# Sheet2.net
KiCad netlist of a schematic drawn in Altium Designer
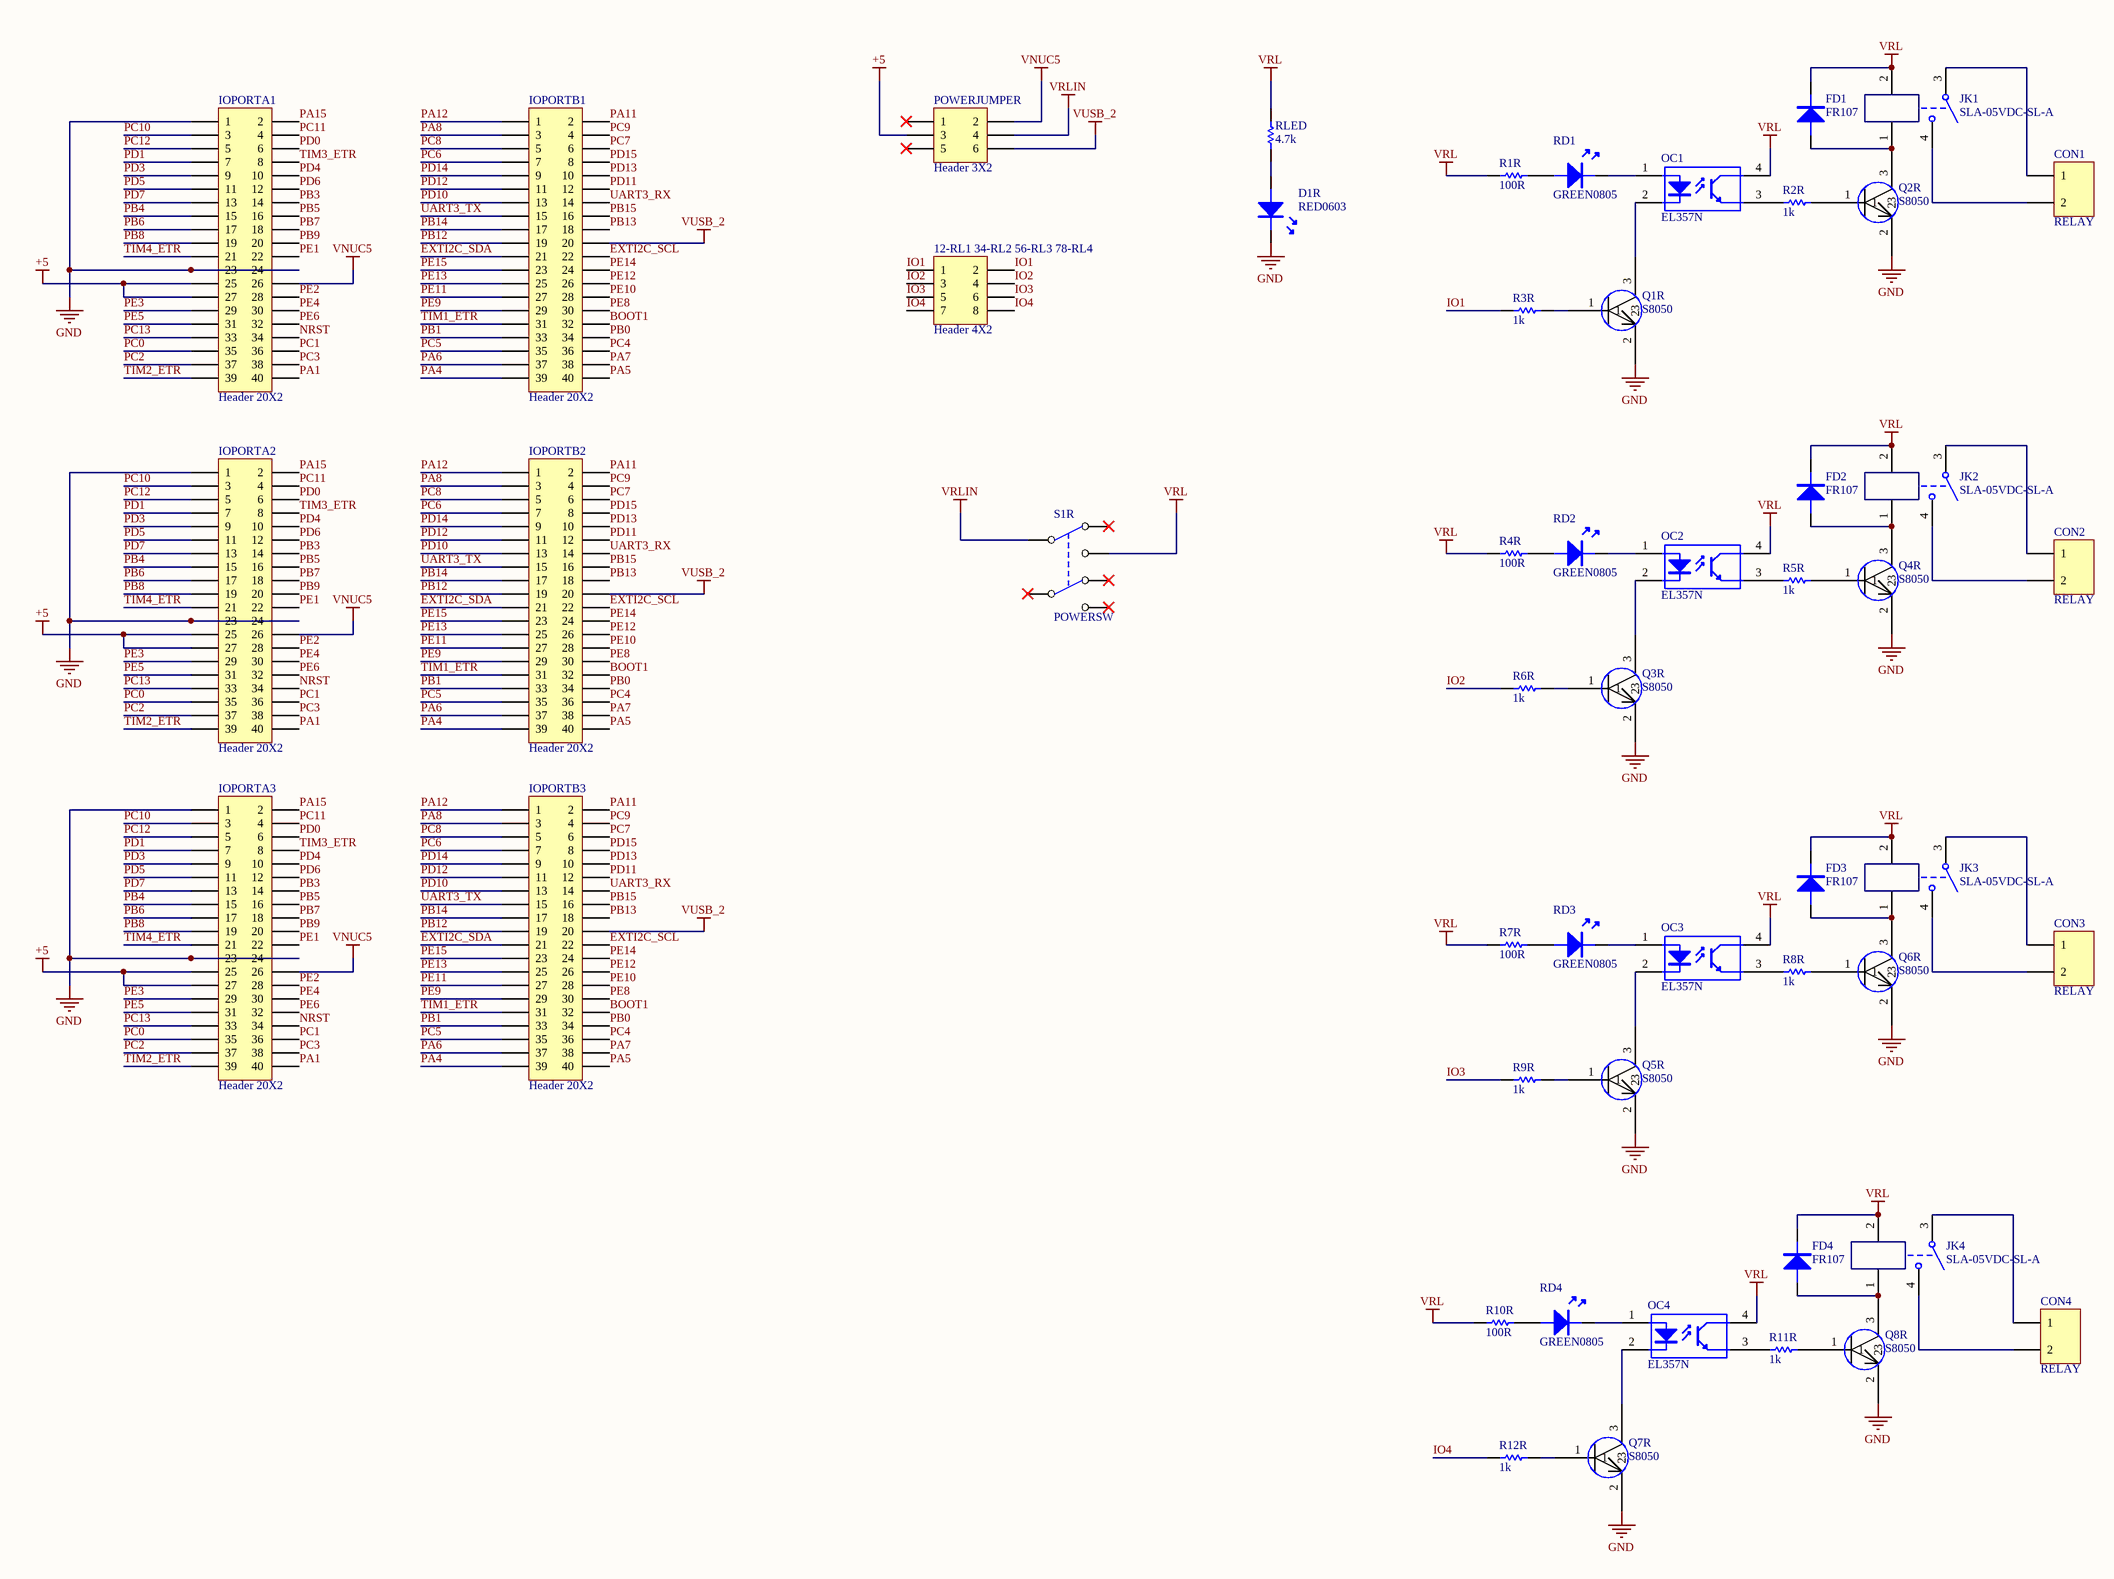
[diagram p0: Sheet2.SchDoc]

(export (version "E")
  (design (tool "Eeschema 10.0.6"))
  (components
    (comp (ref "12-RL1 34-RL2 56-RL3 78-RL4")
      (value "Header 4X2")
      (footprint "HDR2X4")
      (description "Header, 4-Pin, Dual row")
      (fields (field (name "PUBLISHER") "Altium Limited"))
      (libsource (lib "Miscellaneous Connectors") (part "Header 4X2"))
    )
    (comp (ref "CON1") (value "RELAY") (footprint "KF301-2P") (libsource (lib "接线端子") (part "Connector-2P")))
    (comp (ref "CON2") (value "RELAY") (footprint "KF301-2P") (libsource (lib "接线端子") (part "Connector-2P")))
    (comp (ref "CON3") (value "RELAY") (footprint "KF301-2P") (libsource (lib "接线端子") (part "Connector-2P")))
    (comp (ref "CON4") (value "RELAY") (footprint "KF301-2P") (libsource (lib "接线端子") (part "Connector-2P")))
    (comp (ref "D1R") (value "RED0603") (footprint "LED-0603W") (libsource (lib "LED") (part "LED")))
    (comp (ref "FD1")
      (value "FR107")
      (footprint "SOD-123")
      (description "普通二极管")
      (libsource (lib "DIODE") (part "DIODE"))
    )
    (comp (ref "FD2")
      (value "FR107")
      (footprint "SOD-123")
      (description "普通二极管")
      (libsource (lib "DIODE") (part "DIODE"))
    )
    (comp (ref "FD3")
      (value "FR107")
      (footprint "SOD-123")
      (description "普通二极管")
      (libsource (lib "DIODE") (part "DIODE"))
    )
    (comp (ref "FD4")
      (value "FR107")
      (footprint "SOD-123")
      (description "普通二极管")
      (libsource (lib "DIODE") (part "DIODE"))
    )
    (comp (ref "IOPORTA1")
      (value "Header 20X2")
      (footprint "HDR2X20")
      (description "Header, 20-Pin, Dual row")
      (fields (field (name "PUBLISHER") "Altium Limited"))
      (libsource (lib "Miscellaneous Connectors") (part "Header 20X2"))
    )
    (comp (ref "IOPORTA2")
      (value "Header 20X2")
      (footprint "HDR2X20")
      (description "Header, 20-Pin, Dual row")
      (fields (field (name "PUBLISHER") "Altium Limited"))
      (libsource (lib "Miscellaneous Connectors") (part "Header 20X2"))
    )
    (comp (ref "IOPORTA3")
      (value "Header 20X2")
      (footprint "HDR2X20")
      (description "Header, 20-Pin, Dual row")
      (fields (field (name "PUBLISHER") "Altium Limited"))
      (libsource (lib "Miscellaneous Connectors") (part "Header 20X2"))
    )
    (comp (ref "IOPORTB1")
      (value "Header 20X2")
      (footprint "HDR2X20")
      (description "Header, 20-Pin, Dual row")
      (fields (field (name "PUBLISHER") "Altium Limited"))
      (libsource (lib "Miscellaneous Connectors") (part "Header 20X2"))
    )
    (comp (ref "IOPORTB2")
      (value "Header 20X2")
      (footprint "HDR2X20")
      (description "Header, 20-Pin, Dual row")
      (fields (field (name "PUBLISHER") "Altium Limited"))
      (libsource (lib "Miscellaneous Connectors") (part "Header 20X2"))
    )
    (comp (ref "IOPORTB3")
      (value "Header 20X2")
      (footprint "HDR2X20")
      (description "Header, 20-Pin, Dual row")
      (fields (field (name "PUBLISHER") "Altium Limited"))
      (libsource (lib "Miscellaneous Connectors") (part "Header 20X2"))
    )
    (comp (ref "JK1")
      (value "SLA-05VDC-SL-A")
      (footprint "SLA-xxVDC-SL-A")
      (description "5V常开")
      (libsource (lib "REALY") (part "SLA-05VDC-SL-A"))
    )
    (comp (ref "JK2")
      (value "SLA-05VDC-SL-A")
      (footprint "SLA-xxVDC-SL-A")
      (description "5V常开")
      (libsource (lib "REALY") (part "SLA-05VDC-SL-A"))
    )
    (comp (ref "JK3")
      (value "SLA-05VDC-SL-A")
      (footprint "SLA-xxVDC-SL-A")
      (description "5V常开")
      (libsource (lib "REALY") (part "SLA-05VDC-SL-A"))
    )
    (comp (ref "JK4")
      (value "SLA-05VDC-SL-A")
      (footprint "SLA-xxVDC-SL-A")
      (description "5V常开")
      (libsource (lib "REALY") (part "SLA-05VDC-SL-A"))
    )
    (comp (ref "OC1")
      (value "EL357N")
      (footprint "SMD_EL357N")
      (description "线性光耦")
      (libsource (lib "光电隔离器") (part "EL357N"))
    )
    (comp (ref "OC2")
      (value "EL357N")
      (footprint "SMD_EL357N")
      (description "线性光耦")
      (libsource (lib "光电隔离器") (part "EL357N"))
    )
    (comp (ref "OC3")
      (value "EL357N")
      (footprint "SMD_EL357N")
      (description "线性光耦")
      (libsource (lib "光电隔离器") (part "EL357N"))
    )
    (comp (ref "OC4")
      (value "EL357N")
      (footprint "SMD_EL357N")
      (description "线性光耦")
      (libsource (lib "光电隔离器") (part "EL357N"))
    )
    (comp (ref "POWERJUMPER")
      (value "Header 3X2")
      (footprint "HDR2X3")
      (description "Header, 3-Pin, Dual row")
      (fields (field (name "PUBLISHER") "Altium Limited"))
      (libsource (lib "Miscellaneous Connectors") (part "Header 3X2"))
    )
    (comp (ref "Q1R") (value "S8050") (footprint "ics:SOT23") (libsource (lib "ics") (part "S9014")))
    (comp (ref "Q2R") (value "S8050") (footprint "ics:SOT23") (libsource (lib "ics") (part "S9014")))
    (comp (ref "Q3R") (value "S8050") (footprint "ics:SOT23") (libsource (lib "ics") (part "S9014")))
    (comp (ref "Q4R") (value "S8050") (footprint "ics:SOT23") (libsource (lib "ics") (part "S9014")))
    (comp (ref "Q5R") (value "S8050") (footprint "ics:SOT23") (libsource (lib "ics") (part "S9014")))
    (comp (ref "Q6R") (value "S8050") (footprint "ics:SOT23") (libsource (lib "ics") (part "S9014")))
    (comp (ref "Q7R") (value "S8050") (footprint "ics:SOT23") (libsource (lib "ics") (part "S9014")))
    (comp (ref "Q8R") (value "S8050") (footprint "ics:SOT23") (libsource (lib "ics") (part "S9014")))
    (comp (ref "R1R") (value "100R") (footprint "0603R") (libsource (lib "Resistance") (part "RES")))
    (comp (ref "R2R") (value "1k") (footprint "0603R") (libsource (lib "Resistance") (part "RES")))
    (comp (ref "R3R") (value "1k") (footprint "0603R") (libsource (lib "Resistance") (part "RES")))
    (comp (ref "R4R") (value "100R") (footprint "0603R") (libsource (lib "Resistance") (part "RES")))
    (comp (ref "R5R") (value "1k") (footprint "0603R") (libsource (lib "Resistance") (part "RES")))
    (comp (ref "R6R") (value "1k") (footprint "0603R") (libsource (lib "Resistance") (part "RES")))
    (comp (ref "R7R") (value "100R") (footprint "0603R") (libsource (lib "Resistance") (part "RES")))
    (comp (ref "R8R") (value "1k") (footprint "0603R") (libsource (lib "Resistance") (part "RES")))
    (comp (ref "R9R") (value "1k") (footprint "0603R") (libsource (lib "Resistance") (part "RES")))
    (comp (ref "R10R") (value "100R") (footprint "0603R") (libsource (lib "Resistance") (part "RES")))
    (comp (ref "R11R") (value "1k") (footprint "0603R") (libsource (lib "Resistance") (part "RES")))
    (comp (ref "R12R") (value "1k") (footprint "0603R") (libsource (lib "Resistance") (part "RES")))
    (comp (ref "RD1") (value "GREEN0805") (footprint "LED-0805G") (libsource (lib "LED") (part "LED")))
    (comp (ref "RD2") (value "GREEN0805") (footprint "LED-0805G") (libsource (lib "LED") (part "LED")))
    (comp (ref "RD3") (value "GREEN0805") (footprint "LED-0805G") (libsource (lib "LED") (part "LED")))
    (comp (ref "RD4") (value "GREEN0805") (footprint "LED-0805G") (libsource (lib "LED") (part "LED")))
    (comp (ref "RLED") (value "4.7k") (footprint "0603R") (libsource (lib "Resistance") (part "RES")))
    (comp (ref "S1R")
      (value "POWERSW")
      (footprint "KFT DIP-7X7")
      (libsource (lib "电源开关") (part "KFT DIP-7X7"))
    )
  )
  (nets
    (net (code "1") (name "+5") (class "Default")
      (node (ref "IOPORTA1") (pin "25") (pinfunction "25_25") (pintype "passive"))
      (node (ref "IOPORTA1") (pin "27") (pinfunction "27_27") (pintype "passive"))
      (node (ref "IOPORTA2") (pin "25") (pinfunction "25_25") (pintype "passive"))
      (node (ref "IOPORTA2") (pin "27") (pinfunction "27_27") (pintype "passive"))
      (node (ref "IOPORTA3") (pin "25") (pinfunction "25_25") (pintype "passive"))
      (node (ref "IOPORTA3") (pin "27") (pinfunction "27_27") (pintype "passive"))
      (node (ref "POWERJUMPER") (pin "3") (pinfunction "3_3") (pintype "passive"))
    )
    (net (code "2") (name "/BOOT1") (class "Default")
      (node (ref "IOPORTB1") (pin "32") (pinfunction "32_32") (pintype "passive"))
      (node (ref "IOPORTB2") (pin "32") (pinfunction "32_32") (pintype "passive"))
      (node (ref "IOPORTB3") (pin "32") (pinfunction "32_32") (pintype "passive"))
    )
    (net (code "3") (name "/EXTI2C_SCL") (class "Default")
      (node (ref "IOPORTB1") (pin "22") (pinfunction "22_22") (pintype "passive"))
      (node (ref "IOPORTB2") (pin "22") (pinfunction "22_22") (pintype "passive"))
      (node (ref "IOPORTB3") (pin "22") (pinfunction "22_22") (pintype "passive"))
    )
    (net (code "4") (name "/EXTI2C_SDA") (class "Default")
      (node (ref "IOPORTB1") (pin "21") (pinfunction "21_21") (pintype "passive"))
      (node (ref "IOPORTB2") (pin "21") (pinfunction "21_21") (pintype "passive"))
      (node (ref "IOPORTB3") (pin "21") (pinfunction "21_21") (pintype "passive"))
    )
    (net (code "5") (name "/IO1") (class "Default")
      (node (ref "12-RL1 34-RL2 56-RL3 78-RL4") (pin "1") (pinfunction "1_1") (pintype "passive"))
      (node (ref "12-RL1 34-RL2 56-RL3 78-RL4") (pin "2") (pinfunction "2_2") (pintype "passive"))
      (node (ref "R3R") (pin "1") (pinfunction "1_1") (pintype "passive"))
    )
    (net (code "6") (name "/IO2") (class "Default")
      (node (ref "12-RL1 34-RL2 56-RL3 78-RL4") (pin "3") (pinfunction "3_3") (pintype "passive"))
      (node (ref "12-RL1 34-RL2 56-RL3 78-RL4") (pin "4") (pinfunction "4_4") (pintype "passive"))
      (node (ref "R6R") (pin "1") (pinfunction "1_1") (pintype "passive"))
    )
    (net (code "7") (name "/IO3") (class "Default")
      (node (ref "12-RL1 34-RL2 56-RL3 78-RL4") (pin "5") (pinfunction "5_5") (pintype "passive"))
      (node (ref "12-RL1 34-RL2 56-RL3 78-RL4") (pin "6") (pinfunction "6_6") (pintype "passive"))
      (node (ref "R9R") (pin "1") (pinfunction "1_1") (pintype "passive"))
    )
    (net (code "8") (name "/IO4") (class "Default")
      (node (ref "12-RL1 34-RL2 56-RL3 78-RL4") (pin "7") (pinfunction "7_7") (pintype "passive"))
      (node (ref "12-RL1 34-RL2 56-RL3 78-RL4") (pin "8") (pinfunction "8_8") (pintype "passive"))
      (node (ref "R12R") (pin "1") (pinfunction "1_1") (pintype "passive"))
    )
    (net (code "9") (name "/NRST") (class "Default")
      (node (ref "IOPORTA1") (pin "34") (pinfunction "34_34") (pintype "passive"))
      (node (ref "IOPORTA2") (pin "34") (pinfunction "34_34") (pintype "passive"))
      (node (ref "IOPORTA3") (pin "34") (pinfunction "34_34") (pintype "passive"))
    )
    (net (code "10") (name "/PA1") (class "Default")
      (node (ref "IOPORTA1") (pin "40") (pinfunction "40_40") (pintype "passive"))
      (node (ref "IOPORTA2") (pin "40") (pinfunction "40_40") (pintype "passive"))
      (node (ref "IOPORTA3") (pin "40") (pinfunction "40_40") (pintype "passive"))
    )
    (net (code "11") (name "/PA4") (class "Default")
      (node (ref "IOPORTB1") (pin "39") (pinfunction "39_39") (pintype "passive"))
      (node (ref "IOPORTB2") (pin "39") (pinfunction "39_39") (pintype "passive"))
      (node (ref "IOPORTB3") (pin "39") (pinfunction "39_39") (pintype "passive"))
    )
    (net (code "12") (name "/PA5") (class "Default")
      (node (ref "IOPORTB1") (pin "40") (pinfunction "40_40") (pintype "passive"))
      (node (ref "IOPORTB2") (pin "40") (pinfunction "40_40") (pintype "passive"))
      (node (ref "IOPORTB3") (pin "40") (pinfunction "40_40") (pintype "passive"))
    )
    (net (code "13") (name "/PA6") (class "Default")
      (node (ref "IOPORTB1") (pin "37") (pinfunction "37_37") (pintype "passive"))
      (node (ref "IOPORTB2") (pin "37") (pinfunction "37_37") (pintype "passive"))
      (node (ref "IOPORTB3") (pin "37") (pinfunction "37_37") (pintype "passive"))
    )
    (net (code "14") (name "/PA7") (class "Default")
      (node (ref "IOPORTB1") (pin "38") (pinfunction "38_38") (pintype "passive"))
      (node (ref "IOPORTB2") (pin "38") (pinfunction "38_38") (pintype "passive"))
      (node (ref "IOPORTB3") (pin "38") (pinfunction "38_38") (pintype "passive"))
    )
    (net (code "15") (name "/PA8") (class "Default")
      (node (ref "IOPORTB1") (pin "3") (pinfunction "3_3") (pintype "passive"))
      (node (ref "IOPORTB2") (pin "3") (pinfunction "3_3") (pintype "passive"))
      (node (ref "IOPORTB3") (pin "3") (pinfunction "3_3") (pintype "passive"))
    )
    (net (code "16") (name "/PA11") (class "Default")
      (node (ref "IOPORTB1") (pin "2") (pinfunction "2_2") (pintype "passive"))
      (node (ref "IOPORTB2") (pin "2") (pinfunction "2_2") (pintype "passive"))
      (node (ref "IOPORTB3") (pin "2") (pinfunction "2_2") (pintype "passive"))
    )
    (net (code "17") (name "/PA12") (class "Default")
      (node (ref "IOPORTB1") (pin "1") (pinfunction "1_1") (pintype "passive"))
      (node (ref "IOPORTB2") (pin "1") (pinfunction "1_1") (pintype "passive"))
      (node (ref "IOPORTB3") (pin "1") (pinfunction "1_1") (pintype "passive"))
    )
    (net (code "18") (name "/PA15") (class "Default")
      (node (ref "IOPORTA1") (pin "2") (pinfunction "2_2") (pintype "passive"))
      (node (ref "IOPORTA2") (pin "2") (pinfunction "2_2") (pintype "passive"))
      (node (ref "IOPORTA3") (pin "2") (pinfunction "2_2") (pintype "passive"))
    )
    (net (code "19") (name "/PB0") (class "Default")
      (node (ref "IOPORTB1") (pin "34") (pinfunction "34_34") (pintype "passive"))
      (node (ref "IOPORTB2") (pin "34") (pinfunction "34_34") (pintype "passive"))
      (node (ref "IOPORTB3") (pin "34") (pinfunction "34_34") (pintype "passive"))
    )
    (net (code "20") (name "/PB1") (class "Default")
      (node (ref "IOPORTB1") (pin "33") (pinfunction "33_33") (pintype "passive"))
      (node (ref "IOPORTB2") (pin "33") (pinfunction "33_33") (pintype "passive"))
      (node (ref "IOPORTB3") (pin "33") (pinfunction "33_33") (pintype "passive"))
    )
    (net (code "21") (name "/PB3") (class "Default")
      (node (ref "IOPORTA1") (pin "14") (pinfunction "14_14") (pintype "passive"))
      (node (ref "IOPORTA2") (pin "14") (pinfunction "14_14") (pintype "passive"))
      (node (ref "IOPORTA3") (pin "14") (pinfunction "14_14") (pintype "passive"))
    )
    (net (code "22") (name "/PB4") (class "Default")
      (node (ref "IOPORTA1") (pin "15") (pinfunction "15_15") (pintype "passive"))
      (node (ref "IOPORTA2") (pin "15") (pinfunction "15_15") (pintype "passive"))
      (node (ref "IOPORTA3") (pin "15") (pinfunction "15_15") (pintype "passive"))
    )
    (net (code "23") (name "/PB5") (class "Default")
      (node (ref "IOPORTA1") (pin "16") (pinfunction "16_16") (pintype "passive"))
      (node (ref "IOPORTA2") (pin "16") (pinfunction "16_16") (pintype "passive"))
      (node (ref "IOPORTA3") (pin "16") (pinfunction "16_16") (pintype "passive"))
    )
    (net (code "24") (name "/PB6") (class "Default")
      (node (ref "IOPORTA1") (pin "17") (pinfunction "17_17") (pintype "passive"))
      (node (ref "IOPORTA2") (pin "17") (pinfunction "17_17") (pintype "passive"))
      (node (ref "IOPORTA3") (pin "17") (pinfunction "17_17") (pintype "passive"))
    )
    (net (code "25") (name "/PB7") (class "Default")
      (node (ref "IOPORTA1") (pin "18") (pinfunction "18_18") (pintype "passive"))
      (node (ref "IOPORTA2") (pin "18") (pinfunction "18_18") (pintype "passive"))
      (node (ref "IOPORTA3") (pin "18") (pinfunction "18_18") (pintype "passive"))
    )
    (net (code "26") (name "/PB8") (class "Default")
      (node (ref "IOPORTA1") (pin "19") (pinfunction "19_19") (pintype "passive"))
      (node (ref "IOPORTA2") (pin "19") (pinfunction "19_19") (pintype "passive"))
      (node (ref "IOPORTA3") (pin "19") (pinfunction "19_19") (pintype "passive"))
    )
    (net (code "27") (name "/PB9") (class "Default")
      (node (ref "IOPORTA1") (pin "20") (pinfunction "20_20") (pintype "passive"))
      (node (ref "IOPORTA2") (pin "20") (pinfunction "20_20") (pintype "passive"))
      (node (ref "IOPORTA3") (pin "20") (pinfunction "20_20") (pintype "passive"))
    )
    (net (code "28") (name "/PB12") (class "Default")
      (node (ref "IOPORTB1") (pin "19") (pinfunction "19_19") (pintype "passive"))
      (node (ref "IOPORTB2") (pin "19") (pinfunction "19_19") (pintype "passive"))
      (node (ref "IOPORTB3") (pin "19") (pinfunction "19_19") (pintype "passive"))
    )
    (net (code "29") (name "/PB13") (class "Default")
      (node (ref "IOPORTB1") (pin "18") (pinfunction "18_18") (pintype "passive"))
      (node (ref "IOPORTB2") (pin "18") (pinfunction "18_18") (pintype "passive"))
      (node (ref "IOPORTB3") (pin "18") (pinfunction "18_18") (pintype "passive"))
    )
    (net (code "30") (name "/PB14") (class "Default")
      (node (ref "IOPORTB1") (pin "17") (pinfunction "17_17") (pintype "passive"))
      (node (ref "IOPORTB2") (pin "17") (pinfunction "17_17") (pintype "passive"))
      (node (ref "IOPORTB3") (pin "17") (pinfunction "17_17") (pintype "passive"))
    )
    (net (code "31") (name "/PB15") (class "Default")
      (node (ref "IOPORTB1") (pin "16") (pinfunction "16_16") (pintype "passive"))
      (node (ref "IOPORTB2") (pin "16") (pinfunction "16_16") (pintype "passive"))
      (node (ref "IOPORTB3") (pin "16") (pinfunction "16_16") (pintype "passive"))
    )
    (net (code "32") (name "/PC0") (class "Default")
      (node (ref "IOPORTA1") (pin "35") (pinfunction "35_35") (pintype "passive"))
      (node (ref "IOPORTA2") (pin "35") (pinfunction "35_35") (pintype "passive"))
      (node (ref "IOPORTA3") (pin "35") (pinfunction "35_35") (pintype "passive"))
    )
    (net (code "33") (name "/PC1") (class "Default")
      (node (ref "IOPORTA1") (pin "36") (pinfunction "36_36") (pintype "passive"))
      (node (ref "IOPORTA2") (pin "36") (pinfunction "36_36") (pintype "passive"))
      (node (ref "IOPORTA3") (pin "36") (pinfunction "36_36") (pintype "passive"))
    )
    (net (code "34") (name "/PC2") (class "Default")
      (node (ref "IOPORTA1") (pin "37") (pinfunction "37_37") (pintype "passive"))
      (node (ref "IOPORTA2") (pin "37") (pinfunction "37_37") (pintype "passive"))
      (node (ref "IOPORTA3") (pin "37") (pinfunction "37_37") (pintype "passive"))
    )
    (net (code "35") (name "/PC3") (class "Default")
      (node (ref "IOPORTA1") (pin "38") (pinfunction "38_38") (pintype "passive"))
      (node (ref "IOPORTA2") (pin "38") (pinfunction "38_38") (pintype "passive"))
      (node (ref "IOPORTA3") (pin "38") (pinfunction "38_38") (pintype "passive"))
    )
    (net (code "36") (name "/PC4") (class "Default")
      (node (ref "IOPORTB1") (pin "36") (pinfunction "36_36") (pintype "passive"))
      (node (ref "IOPORTB2") (pin "36") (pinfunction "36_36") (pintype "passive"))
      (node (ref "IOPORTB3") (pin "36") (pinfunction "36_36") (pintype "passive"))
    )
    (net (code "37") (name "/PC5") (class "Default")
      (node (ref "IOPORTB1") (pin "35") (pinfunction "35_35") (pintype "passive"))
      (node (ref "IOPORTB2") (pin "35") (pinfunction "35_35") (pintype "passive"))
      (node (ref "IOPORTB3") (pin "35") (pinfunction "35_35") (pintype "passive"))
    )
    (net (code "38") (name "/PC6") (class "Default")
      (node (ref "IOPORTB1") (pin "7") (pinfunction "7_7") (pintype "passive"))
      (node (ref "IOPORTB2") (pin "7") (pinfunction "7_7") (pintype "passive"))
      (node (ref "IOPORTB3") (pin "7") (pinfunction "7_7") (pintype "passive"))
    )
    (net (code "39") (name "/PC7") (class "Default")
      (node (ref "IOPORTB1") (pin "6") (pinfunction "6_6") (pintype "passive"))
      (node (ref "IOPORTB2") (pin "6") (pinfunction "6_6") (pintype "passive"))
      (node (ref "IOPORTB3") (pin "6") (pinfunction "6_6") (pintype "passive"))
    )
    (net (code "40") (name "/PC8") (class "Default")
      (node (ref "IOPORTB1") (pin "5") (pinfunction "5_5") (pintype "passive"))
      (node (ref "IOPORTB2") (pin "5") (pinfunction "5_5") (pintype "passive"))
      (node (ref "IOPORTB3") (pin "5") (pinfunction "5_5") (pintype "passive"))
    )
    (net (code "41") (name "/PC9") (class "Default")
      (node (ref "IOPORTB1") (pin "4") (pinfunction "4_4") (pintype "passive"))
      (node (ref "IOPORTB2") (pin "4") (pinfunction "4_4") (pintype "passive"))
      (node (ref "IOPORTB3") (pin "4") (pinfunction "4_4") (pintype "passive"))
    )
    (net (code "42") (name "/PC10") (class "Default")
      (node (ref "IOPORTA1") (pin "3") (pinfunction "3_3") (pintype "passive"))
      (node (ref "IOPORTA2") (pin "3") (pinfunction "3_3") (pintype "passive"))
      (node (ref "IOPORTA3") (pin "3") (pinfunction "3_3") (pintype "passive"))
    )
    (net (code "43") (name "/PC11") (class "Default")
      (node (ref "IOPORTA1") (pin "4") (pinfunction "4_4") (pintype "passive"))
      (node (ref "IOPORTA2") (pin "4") (pinfunction "4_4") (pintype "passive"))
      (node (ref "IOPORTA3") (pin "4") (pinfunction "4_4") (pintype "passive"))
    )
    (net (code "44") (name "/PC12") (class "Default")
      (node (ref "IOPORTA1") (pin "5") (pinfunction "5_5") (pintype "passive"))
      (node (ref "IOPORTA2") (pin "5") (pinfunction "5_5") (pintype "passive"))
      (node (ref "IOPORTA3") (pin "5") (pinfunction "5_5") (pintype "passive"))
    )
    (net (code "45") (name "/PC13") (class "Default")
      (node (ref "IOPORTA1") (pin "33") (pinfunction "33_33") (pintype "passive"))
      (node (ref "IOPORTA2") (pin "33") (pinfunction "33_33") (pintype "passive"))
      (node (ref "IOPORTA3") (pin "33") (pinfunction "33_33") (pintype "passive"))
    )
    (net (code "46") (name "/PD0") (class "Default")
      (node (ref "IOPORTA1") (pin "6") (pinfunction "6_6") (pintype "passive"))
      (node (ref "IOPORTA2") (pin "6") (pinfunction "6_6") (pintype "passive"))
      (node (ref "IOPORTA3") (pin "6") (pinfunction "6_6") (pintype "passive"))
    )
    (net (code "47") (name "/PD1") (class "Default")
      (node (ref "IOPORTA1") (pin "7") (pinfunction "7_7") (pintype "passive"))
      (node (ref "IOPORTA2") (pin "7") (pinfunction "7_7") (pintype "passive"))
      (node (ref "IOPORTA3") (pin "7") (pinfunction "7_7") (pintype "passive"))
    )
    (net (code "48") (name "/PD3") (class "Default")
      (node (ref "IOPORTA1") (pin "9") (pinfunction "9_9") (pintype "passive"))
      (node (ref "IOPORTA2") (pin "9") (pinfunction "9_9") (pintype "passive"))
      (node (ref "IOPORTA3") (pin "9") (pinfunction "9_9") (pintype "passive"))
    )
    (net (code "49") (name "/PD4") (class "Default")
      (node (ref "IOPORTA1") (pin "10") (pinfunction "10_10") (pintype "passive"))
      (node (ref "IOPORTA2") (pin "10") (pinfunction "10_10") (pintype "passive"))
      (node (ref "IOPORTA3") (pin "10") (pinfunction "10_10") (pintype "passive"))
    )
    (net (code "50") (name "/PD5") (class "Default")
      (node (ref "IOPORTA1") (pin "11") (pinfunction "11_11") (pintype "passive"))
      (node (ref "IOPORTA2") (pin "11") (pinfunction "11_11") (pintype "passive"))
      (node (ref "IOPORTA3") (pin "11") (pinfunction "11_11") (pintype "passive"))
    )
    (net (code "51") (name "/PD6") (class "Default")
      (node (ref "IOPORTA1") (pin "12") (pinfunction "12_12") (pintype "passive"))
      (node (ref "IOPORTA2") (pin "12") (pinfunction "12_12") (pintype "passive"))
      (node (ref "IOPORTA3") (pin "12") (pinfunction "12_12") (pintype "passive"))
    )
    (net (code "52") (name "/PD7") (class "Default")
      (node (ref "IOPORTA1") (pin "13") (pinfunction "13_13") (pintype "passive"))
      (node (ref "IOPORTA2") (pin "13") (pinfunction "13_13") (pintype "passive"))
      (node (ref "IOPORTA3") (pin "13") (pinfunction "13_13") (pintype "passive"))
    )
    (net (code "53") (name "/PD10") (class "Default")
      (node (ref "IOPORTB1") (pin "13") (pinfunction "13_13") (pintype "passive"))
      (node (ref "IOPORTB2") (pin "13") (pinfunction "13_13") (pintype "passive"))
      (node (ref "IOPORTB3") (pin "13") (pinfunction "13_13") (pintype "passive"))
    )
    (net (code "54") (name "/PD11") (class "Default")
      (node (ref "IOPORTB1") (pin "12") (pinfunction "12_12") (pintype "passive"))
      (node (ref "IOPORTB2") (pin "12") (pinfunction "12_12") (pintype "passive"))
      (node (ref "IOPORTB3") (pin "12") (pinfunction "12_12") (pintype "passive"))
    )
    (net (code "55") (name "/PD12") (class "Default")
      (node (ref "IOPORTB1") (pin "11") (pinfunction "11_11") (pintype "passive"))
      (node (ref "IOPORTB2") (pin "11") (pinfunction "11_11") (pintype "passive"))
      (node (ref "IOPORTB3") (pin "11") (pinfunction "11_11") (pintype "passive"))
    )
    (net (code "56") (name "/PD13") (class "Default")
      (node (ref "IOPORTB1") (pin "10") (pinfunction "10_10") (pintype "passive"))
      (node (ref "IOPORTB2") (pin "10") (pinfunction "10_10") (pintype "passive"))
      (node (ref "IOPORTB3") (pin "10") (pinfunction "10_10") (pintype "passive"))
    )
    (net (code "57") (name "/PD14") (class "Default")
      (node (ref "IOPORTB1") (pin "9") (pinfunction "9_9") (pintype "passive"))
      (node (ref "IOPORTB2") (pin "9") (pinfunction "9_9") (pintype "passive"))
      (node (ref "IOPORTB3") (pin "9") (pinfunction "9_9") (pintype "passive"))
    )
    (net (code "58") (name "/PD15") (class "Default")
      (node (ref "IOPORTB1") (pin "8") (pinfunction "8_8") (pintype "passive"))
      (node (ref "IOPORTB2") (pin "8") (pinfunction "8_8") (pintype "passive"))
      (node (ref "IOPORTB3") (pin "8") (pinfunction "8_8") (pintype "passive"))
    )
    (net (code "59") (name "/PE1") (class "Default")
      (node (ref "IOPORTA1") (pin "22") (pinfunction "22_22") (pintype "passive"))
      (node (ref "IOPORTA2") (pin "22") (pinfunction "22_22") (pintype "passive"))
      (node (ref "IOPORTA3") (pin "22") (pinfunction "22_22") (pintype "passive"))
    )
    (net (code "60") (name "/PE2") (class "Default")
      (node (ref "IOPORTA1") (pin "28") (pinfunction "28_28") (pintype "passive"))
      (node (ref "IOPORTA2") (pin "28") (pinfunction "28_28") (pintype "passive"))
      (node (ref "IOPORTA3") (pin "28") (pinfunction "28_28") (pintype "passive"))
    )
    (net (code "61") (name "/PE3") (class "Default")
      (node (ref "IOPORTA1") (pin "29") (pinfunction "29_29") (pintype "passive"))
      (node (ref "IOPORTA2") (pin "29") (pinfunction "29_29") (pintype "passive"))
      (node (ref "IOPORTA3") (pin "29") (pinfunction "29_29") (pintype "passive"))
    )
    (net (code "62") (name "/PE4") (class "Default")
      (node (ref "IOPORTA1") (pin "30") (pinfunction "30_30") (pintype "passive"))
      (node (ref "IOPORTA2") (pin "30") (pinfunction "30_30") (pintype "passive"))
      (node (ref "IOPORTA3") (pin "30") (pinfunction "30_30") (pintype "passive"))
    )
    (net (code "63") (name "/PE5") (class "Default")
      (node (ref "IOPORTA1") (pin "31") (pinfunction "31_31") (pintype "passive"))
      (node (ref "IOPORTA2") (pin "31") (pinfunction "31_31") (pintype "passive"))
      (node (ref "IOPORTA3") (pin "31") (pinfunction "31_31") (pintype "passive"))
    )
    (net (code "64") (name "/PE6") (class "Default")
      (node (ref "IOPORTA1") (pin "32") (pinfunction "32_32") (pintype "passive"))
      (node (ref "IOPORTA2") (pin "32") (pinfunction "32_32") (pintype "passive"))
      (node (ref "IOPORTA3") (pin "32") (pinfunction "32_32") (pintype "passive"))
    )
    (net (code "65") (name "/PE8") (class "Default")
      (node (ref "IOPORTB1") (pin "30") (pinfunction "30_30") (pintype "passive"))
      (node (ref "IOPORTB2") (pin "30") (pinfunction "30_30") (pintype "passive"))
      (node (ref "IOPORTB3") (pin "30") (pinfunction "30_30") (pintype "passive"))
    )
    (net (code "66") (name "/PE9") (class "Default")
      (node (ref "IOPORTB1") (pin "29") (pinfunction "29_29") (pintype "passive"))
      (node (ref "IOPORTB2") (pin "29") (pinfunction "29_29") (pintype "passive"))
      (node (ref "IOPORTB3") (pin "29") (pinfunction "29_29") (pintype "passive"))
    )
    (net (code "67") (name "/PE10") (class "Default")
      (node (ref "IOPORTB1") (pin "28") (pinfunction "28_28") (pintype "passive"))
      (node (ref "IOPORTB2") (pin "28") (pinfunction "28_28") (pintype "passive"))
      (node (ref "IOPORTB3") (pin "28") (pinfunction "28_28") (pintype "passive"))
    )
    (net (code "68") (name "/PE11") (class "Default")
      (node (ref "IOPORTB1") (pin "27") (pinfunction "27_27") (pintype "passive"))
      (node (ref "IOPORTB2") (pin "27") (pinfunction "27_27") (pintype "passive"))
      (node (ref "IOPORTB3") (pin "27") (pinfunction "27_27") (pintype "passive"))
    )
    (net (code "69") (name "/PE12") (class "Default")
      (node (ref "IOPORTB1") (pin "26") (pinfunction "26_26") (pintype "passive"))
      (node (ref "IOPORTB2") (pin "26") (pinfunction "26_26") (pintype "passive"))
      (node (ref "IOPORTB3") (pin "26") (pinfunction "26_26") (pintype "passive"))
    )
    (net (code "70") (name "/PE13") (class "Default")
      (node (ref "IOPORTB1") (pin "25") (pinfunction "25_25") (pintype "passive"))
      (node (ref "IOPORTB2") (pin "25") (pinfunction "25_25") (pintype "passive"))
      (node (ref "IOPORTB3") (pin "25") (pinfunction "25_25") (pintype "passive"))
    )
    (net (code "71") (name "/PE14") (class "Default")
      (node (ref "IOPORTB1") (pin "24") (pinfunction "24_24") (pintype "passive"))
      (node (ref "IOPORTB2") (pin "24") (pinfunction "24_24") (pintype "passive"))
      (node (ref "IOPORTB3") (pin "24") (pinfunction "24_24") (pintype "passive"))
    )
    (net (code "72") (name "/PE15") (class "Default")
      (node (ref "IOPORTB1") (pin "23") (pinfunction "23_23") (pintype "passive"))
      (node (ref "IOPORTB2") (pin "23") (pinfunction "23_23") (pintype "passive"))
      (node (ref "IOPORTB3") (pin "23") (pinfunction "23_23") (pintype "passive"))
    )
    (net (code "73") (name "/TIM1_ETR") (class "Default")
      (node (ref "IOPORTB1") (pin "31") (pinfunction "31_31") (pintype "passive"))
      (node (ref "IOPORTB2") (pin "31") (pinfunction "31_31") (pintype "passive"))
      (node (ref "IOPORTB3") (pin "31") (pinfunction "31_31") (pintype "passive"))
    )
    (net (code "74") (name "/TIM2_ETR") (class "Default")
      (node (ref "IOPORTA1") (pin "39") (pinfunction "39_39") (pintype "passive"))
      (node (ref "IOPORTA2") (pin "39") (pinfunction "39_39") (pintype "passive"))
      (node (ref "IOPORTA3") (pin "39") (pinfunction "39_39") (pintype "passive"))
    )
    (net (code "75") (name "/TIM3_ETR") (class "Default")
      (node (ref "IOPORTA1") (pin "8") (pinfunction "8_8") (pintype "passive"))
      (node (ref "IOPORTA2") (pin "8") (pinfunction "8_8") (pintype "passive"))
      (node (ref "IOPORTA3") (pin "8") (pinfunction "8_8") (pintype "passive"))
    )
    (net (code "76") (name "/TIM4_ETR") (class "Default")
      (node (ref "IOPORTA1") (pin "21") (pinfunction "21_21") (pintype "passive"))
      (node (ref "IOPORTA2") (pin "21") (pinfunction "21_21") (pintype "passive"))
      (node (ref "IOPORTA3") (pin "21") (pinfunction "21_21") (pintype "passive"))
    )
    (net (code "77") (name "/UART3_RX") (class "Default")
      (node (ref "IOPORTB1") (pin "14") (pinfunction "14_14") (pintype "passive"))
      (node (ref "IOPORTB2") (pin "14") (pinfunction "14_14") (pintype "passive"))
      (node (ref "IOPORTB3") (pin "14") (pinfunction "14_14") (pintype "passive"))
    )
    (net (code "78") (name "/UART3_TX") (class "Default")
      (node (ref "IOPORTB1") (pin "15") (pinfunction "15_15") (pintype "passive"))
      (node (ref "IOPORTB2") (pin "15") (pinfunction "15_15") (pintype "passive"))
      (node (ref "IOPORTB3") (pin "15") (pinfunction "15_15") (pintype "passive"))
    )
    (net (code "79") (name "GND") (class "Default")
      (node (ref "D1R") (pin "K") (pinfunction "K_K") (pintype "passive"))
      (node (ref "IOPORTA1") (pin "1") (pinfunction "1_1") (pintype "passive"))
      (node (ref "IOPORTA1") (pin "23") (pinfunction "23_23") (pintype "passive"))
      (node (ref "IOPORTA1") (pin "24") (pinfunction "24_24") (pintype "passive"))
      (node (ref "IOPORTA2") (pin "1") (pinfunction "1_1") (pintype "passive"))
      (node (ref "IOPORTA2") (pin "23") (pinfunction "23_23") (pintype "passive"))
      (node (ref "IOPORTA2") (pin "24") (pinfunction "24_24") (pintype "passive"))
      (node (ref "IOPORTA3") (pin "1") (pinfunction "1_1") (pintype "passive"))
      (node (ref "IOPORTA3") (pin "23") (pinfunction "23_23") (pintype "passive"))
      (node (ref "IOPORTA3") (pin "24") (pinfunction "24_24") (pintype "passive"))
      (node (ref "Q1R") (pin "2") (pinfunction "2_2") (pintype "passive"))
      (node (ref "Q2R") (pin "2") (pinfunction "2_2") (pintype "passive"))
      (node (ref "Q3R") (pin "2") (pinfunction "2_2") (pintype "passive"))
      (node (ref "Q4R") (pin "2") (pinfunction "2_2") (pintype "passive"))
      (node (ref "Q5R") (pin "2") (pinfunction "2_2") (pintype "passive"))
      (node (ref "Q6R") (pin "2") (pinfunction "2_2") (pintype "passive"))
      (node (ref "Q7R") (pin "2") (pinfunction "2_2") (pintype "passive"))
      (node (ref "Q8R") (pin "2") (pinfunction "2_2") (pintype "passive"))
    )
    (net (code "80") (name "Net-(CON1-Pad1)") (class "Default")
      (node (ref "CON1") (pin "1") (pinfunction "1_1") (pintype "passive"))
      (node (ref "JK1") (pin "3") (pinfunction "3_3") (pintype "passive"))
    )
    (net (code "81") (name "Net-(CON1-Pad2)") (class "Default")
      (node (ref "CON1") (pin "2") (pinfunction "2_2") (pintype "passive"))
      (node (ref "JK1") (pin "4") (pinfunction "4_4") (pintype "passive"))
    )
    (net (code "82") (name "Net-(CON2-Pad1)") (class "Default")
      (node (ref "CON2") (pin "1") (pinfunction "1_1") (pintype "passive"))
      (node (ref "JK2") (pin "3") (pinfunction "3_3") (pintype "passive"))
    )
    (net (code "83") (name "Net-(CON2-Pad2)") (class "Default")
      (node (ref "CON2") (pin "2") (pinfunction "2_2") (pintype "passive"))
      (node (ref "JK2") (pin "4") (pinfunction "4_4") (pintype "passive"))
    )
    (net (code "84") (name "Net-(CON3-Pad1)") (class "Default")
      (node (ref "CON3") (pin "1") (pinfunction "1_1") (pintype "passive"))
      (node (ref "JK3") (pin "3") (pinfunction "3_3") (pintype "passive"))
    )
    (net (code "85") (name "Net-(CON3-Pad2)") (class "Default")
      (node (ref "CON3") (pin "2") (pinfunction "2_2") (pintype "passive"))
      (node (ref "JK3") (pin "4") (pinfunction "4_4") (pintype "passive"))
    )
    (net (code "86") (name "Net-(CON4-Pad1)") (class "Default")
      (node (ref "CON4") (pin "1") (pinfunction "1_1") (pintype "passive"))
      (node (ref "JK4") (pin "3") (pinfunction "3_3") (pintype "passive"))
    )
    (net (code "87") (name "Net-(CON4-Pad2)") (class "Default")
      (node (ref "CON4") (pin "2") (pinfunction "2_2") (pintype "passive"))
      (node (ref "JK4") (pin "4") (pinfunction "4_4") (pintype "passive"))
    )
    (net (code "88") (name "Net-(D1R-PadA)") (class "Default")
      (node (ref "D1R") (pin "A") (pinfunction "A_A") (pintype "passive"))
      (node (ref "RLED") (pin "1") (pinfunction "1_1") (pintype "passive"))
    )
    (net (code "89") (name "Net-(FD1-PadA)") (class "Default")
      (node (ref "FD1") (pin "A") (pinfunction "A_A") (pintype "passive"))
      (node (ref "JK1") (pin "1") (pinfunction "1_1") (pintype "passive"))
      (node (ref "Q2R") (pin "3") (pinfunction "3_3") (pintype "passive"))
    )
    (net (code "90") (name "Net-(FD2-PadA)") (class "Default")
      (node (ref "FD2") (pin "A") (pinfunction "A_A") (pintype "passive"))
      (node (ref "JK2") (pin "1") (pinfunction "1_1") (pintype "passive"))
      (node (ref "Q4R") (pin "3") (pinfunction "3_3") (pintype "passive"))
    )
    (net (code "91") (name "Net-(FD3-PadA)") (class "Default")
      (node (ref "FD3") (pin "A") (pinfunction "A_A") (pintype "passive"))
      (node (ref "JK3") (pin "1") (pinfunction "1_1") (pintype "passive"))
      (node (ref "Q6R") (pin "3") (pinfunction "3_3") (pintype "passive"))
    )
    (net (code "92") (name "Net-(FD4-PadA)") (class "Default")
      (node (ref "FD4") (pin "A") (pinfunction "A_A") (pintype "passive"))
      (node (ref "JK4") (pin "1") (pinfunction "1_1") (pintype "passive"))
      (node (ref "Q8R") (pin "3") (pinfunction "3_3") (pintype "passive"))
    )
    (net (code "93") (name "Net-(OC1-A)") (class "Default")
      (node (ref "OC1") (pin "1") (pinfunction "A_1") (pintype "passive"))
      (node (ref "RD1") (pin "K") (pinfunction "K_K") (pintype "passive"))
    )
    (net (code "94") (name "Net-(OC1-E)") (class "Default")
      (node (ref "OC1") (pin "3") (pinfunction "E_3") (pintype "passive"))
      (node (ref "R2R") (pin "1") (pinfunction "1_1") (pintype "passive"))
    )
    (net (code "95") (name "Net-(OC1-K)") (class "Default")
      (node (ref "OC1") (pin "2") (pinfunction "K_2") (pintype "passive"))
      (node (ref "Q1R") (pin "3") (pinfunction "3_3") (pintype "passive"))
    )
    (net (code "96") (name "Net-(OC2-A)") (class "Default")
      (node (ref "OC2") (pin "1") (pinfunction "A_1") (pintype "passive"))
      (node (ref "RD2") (pin "K") (pinfunction "K_K") (pintype "passive"))
    )
    (net (code "97") (name "Net-(OC2-E)") (class "Default")
      (node (ref "OC2") (pin "3") (pinfunction "E_3") (pintype "passive"))
      (node (ref "R5R") (pin "1") (pinfunction "1_1") (pintype "passive"))
    )
    (net (code "98") (name "Net-(OC2-K)") (class "Default")
      (node (ref "OC2") (pin "2") (pinfunction "K_2") (pintype "passive"))
      (node (ref "Q3R") (pin "3") (pinfunction "3_3") (pintype "passive"))
    )
    (net (code "99") (name "Net-(OC3-A)") (class "Default")
      (node (ref "OC3") (pin "1") (pinfunction "A_1") (pintype "passive"))
      (node (ref "RD3") (pin "K") (pinfunction "K_K") (pintype "passive"))
    )
    (net (code "100") (name "Net-(OC3-E)") (class "Default")
      (node (ref "OC3") (pin "3") (pinfunction "E_3") (pintype "passive"))
      (node (ref "R8R") (pin "1") (pinfunction "1_1") (pintype "passive"))
    )
    (net (code "101") (name "Net-(OC3-K)") (class "Default")
      (node (ref "OC3") (pin "2") (pinfunction "K_2") (pintype "passive"))
      (node (ref "Q5R") (pin "3") (pinfunction "3_3") (pintype "passive"))
    )
    (net (code "102") (name "Net-(OC4-A)") (class "Default")
      (node (ref "OC4") (pin "1") (pinfunction "A_1") (pintype "passive"))
      (node (ref "RD4") (pin "K") (pinfunction "K_K") (pintype "passive"))
    )
    (net (code "103") (name "Net-(OC4-E)") (class "Default")
      (node (ref "OC4") (pin "3") (pinfunction "E_3") (pintype "passive"))
      (node (ref "R11R") (pin "1") (pinfunction "1_1") (pintype "passive"))
    )
    (net (code "104") (name "Net-(OC4-K)") (class "Default")
      (node (ref "OC4") (pin "2") (pinfunction "K_2") (pintype "passive"))
      (node (ref "Q7R") (pin "3") (pinfunction "3_3") (pintype "passive"))
    )
    (net (code "105") (name "Net-(Q1R-Pad1)") (class "Default")
      (node (ref "Q1R") (pin "1") (pinfunction "1_1") (pintype "passive"))
      (node (ref "R3R") (pin "2") (pinfunction "2_2") (pintype "passive"))
    )
    (net (code "106") (name "Net-(Q2R-Pad1)") (class "Default")
      (node (ref "Q2R") (pin "1") (pinfunction "1_1") (pintype "passive"))
      (node (ref "R2R") (pin "2") (pinfunction "2_2") (pintype "passive"))
    )
    (net (code "107") (name "Net-(Q3R-Pad1)") (class "Default")
      (node (ref "Q3R") (pin "1") (pinfunction "1_1") (pintype "passive"))
      (node (ref "R6R") (pin "2") (pinfunction "2_2") (pintype "passive"))
    )
    (net (code "108") (name "Net-(Q4R-Pad1)") (class "Default")
      (node (ref "Q4R") (pin "1") (pinfunction "1_1") (pintype "passive"))
      (node (ref "R5R") (pin "2") (pinfunction "2_2") (pintype "passive"))
    )
    (net (code "109") (name "Net-(Q5R-Pad1)") (class "Default")
      (node (ref "Q5R") (pin "1") (pinfunction "1_1") (pintype "passive"))
      (node (ref "R9R") (pin "2") (pinfunction "2_2") (pintype "passive"))
    )
    (net (code "110") (name "Net-(Q6R-Pad1)") (class "Default")
      (node (ref "Q6R") (pin "1") (pinfunction "1_1") (pintype "passive"))
      (node (ref "R8R") (pin "2") (pinfunction "2_2") (pintype "passive"))
    )
    (net (code "111") (name "Net-(Q7R-Pad1)") (class "Default")
      (node (ref "Q7R") (pin "1") (pinfunction "1_1") (pintype "passive"))
      (node (ref "R12R") (pin "2") (pinfunction "2_2") (pintype "passive"))
    )
    (net (code "112") (name "Net-(Q8R-Pad1)") (class "Default")
      (node (ref "Q8R") (pin "1") (pinfunction "1_1") (pintype "passive"))
      (node (ref "R11R") (pin "2") (pinfunction "2_2") (pintype "passive"))
    )
    (net (code "113") (name "Net-(R1R-Pad2)") (class "Default")
      (node (ref "R1R") (pin "2") (pinfunction "2_2") (pintype "passive"))
      (node (ref "RD1") (pin "A") (pinfunction "A_A") (pintype "passive"))
    )
    (net (code "114") (name "Net-(R4R-Pad2)") (class "Default")
      (node (ref "R4R") (pin "2") (pinfunction "2_2") (pintype "passive"))
      (node (ref "RD2") (pin "A") (pinfunction "A_A") (pintype "passive"))
    )
    (net (code "115") (name "Net-(R7R-Pad2)") (class "Default")
      (node (ref "R7R") (pin "2") (pinfunction "2_2") (pintype "passive"))
      (node (ref "RD3") (pin "A") (pinfunction "A_A") (pintype "passive"))
    )
    (net (code "116") (name "Net-(R10R-Pad2)") (class "Default")
      (node (ref "R10R") (pin "2") (pinfunction "2_2") (pintype "passive"))
      (node (ref "RD4") (pin "A") (pinfunction "A_A") (pintype "passive"))
    )
    (net (code "117") (name "VNUC5") (class "Default")
      (node (ref "IOPORTA1") (pin "26") (pinfunction "26_26") (pintype "passive"))
      (node (ref "IOPORTA2") (pin "26") (pinfunction "26_26") (pintype "passive"))
      (node (ref "IOPORTA3") (pin "26") (pinfunction "26_26") (pintype "passive"))
      (node (ref "POWERJUMPER") (pin "2") (pinfunction "2_2") (pintype "passive"))
    )
    (net (code "118") (name "VRL") (class "Default")
      (node (ref "FD1") (pin "K") (pinfunction "K_K") (pintype "passive"))
      (node (ref "FD2") (pin "K") (pinfunction "K_K") (pintype "passive"))
      (node (ref "FD3") (pin "K") (pinfunction "K_K") (pintype "passive"))
      (node (ref "FD4") (pin "K") (pinfunction "K_K") (pintype "passive"))
      (node (ref "JK1") (pin "2") (pinfunction "2_2") (pintype "passive"))
      (node (ref "JK2") (pin "2") (pinfunction "2_2") (pintype "passive"))
      (node (ref "JK3") (pin "2") (pinfunction "2_2") (pintype "passive"))
      (node (ref "JK4") (pin "2") (pinfunction "2_2") (pintype "passive"))
      (node (ref "OC1") (pin "4") (pinfunction "C_4") (pintype "passive"))
      (node (ref "OC2") (pin "4") (pinfunction "C_4") (pintype "passive"))
      (node (ref "OC3") (pin "4") (pinfunction "C_4") (pintype "passive"))
      (node (ref "OC4") (pin "4") (pinfunction "C_4") (pintype "passive"))
      (node (ref "R10R") (pin "1") (pinfunction "1_1") (pintype "passive"))
      (node (ref "R1R") (pin "1") (pinfunction "1_1") (pintype "passive"))
      (node (ref "R4R") (pin "1") (pinfunction "1_1") (pintype "passive"))
      (node (ref "R7R") (pin "1") (pinfunction "1_1") (pintype "passive"))
      (node (ref "RLED") (pin "2") (pinfunction "2_2") (pintype "passive"))
      (node (ref "S1R") (pin "1") (pinfunction "1_1") (pintype "passive"))
    )
    (net (code "119") (name "VRLIN") (class "Default")
      (node (ref "POWERJUMPER") (pin "4") (pinfunction "4_4") (pintype "passive"))
      (node (ref "S1R") (pin "2") (pinfunction "2_2") (pintype "passive"))
    )
    (net (code "120") (name "VUSB_2") (class "Default")
      (node (ref "IOPORTB1") (pin "20") (pinfunction "20_20") (pintype "passive"))
      (node (ref "IOPORTB2") (pin "20") (pinfunction "20_20") (pintype "passive"))
      (node (ref "IOPORTB3") (pin "20") (pinfunction "20_20") (pintype "passive"))
      (node (ref "POWERJUMPER") (pin "6") (pinfunction "6_6") (pintype "passive"))
    )
    (net (code "121") (name "unconnected-(POWERJUMPER-Pad1)") (class "Default")
      (node (ref "POWERJUMPER") (pin "1") (pinfunction "1_1") (pintype "passive+no_connect"))
    )
    (net (code "122") (name "unconnected-(POWERJUMPER-Pad5)") (class "Default")
      (node (ref "POWERJUMPER") (pin "5") (pinfunction "5_5") (pintype "passive+no_connect"))
    )
    (net (code "123") (name "unconnected-(S1R-Pad3)") (class "Default")
      (node (ref "S1R") (pin "3") (pinfunction "3_3") (pintype "passive+no_connect"))
    )
    (net (code "124") (name "unconnected-(S1R-Pad4)") (class "Default")
      (node (ref "S1R") (pin "4") (pinfunction "4_4") (pintype "passive+no_connect"))
    )
    (net (code "125") (name "unconnected-(S1R-Pad5)") (class "Default")
      (node (ref "S1R") (pin "5") (pinfunction "5_5") (pintype "passive+no_connect"))
    )
    (net (code "126") (name "unconnected-(S1R-Pad6)") (class "Default")
      (node (ref "S1R") (pin "6") (pinfunction "6_6") (pintype "passive+no_connect"))
    )
  )
)
